# Comm_SQUID.net
KiCad netlist of a schematic drawn in Altium Designer
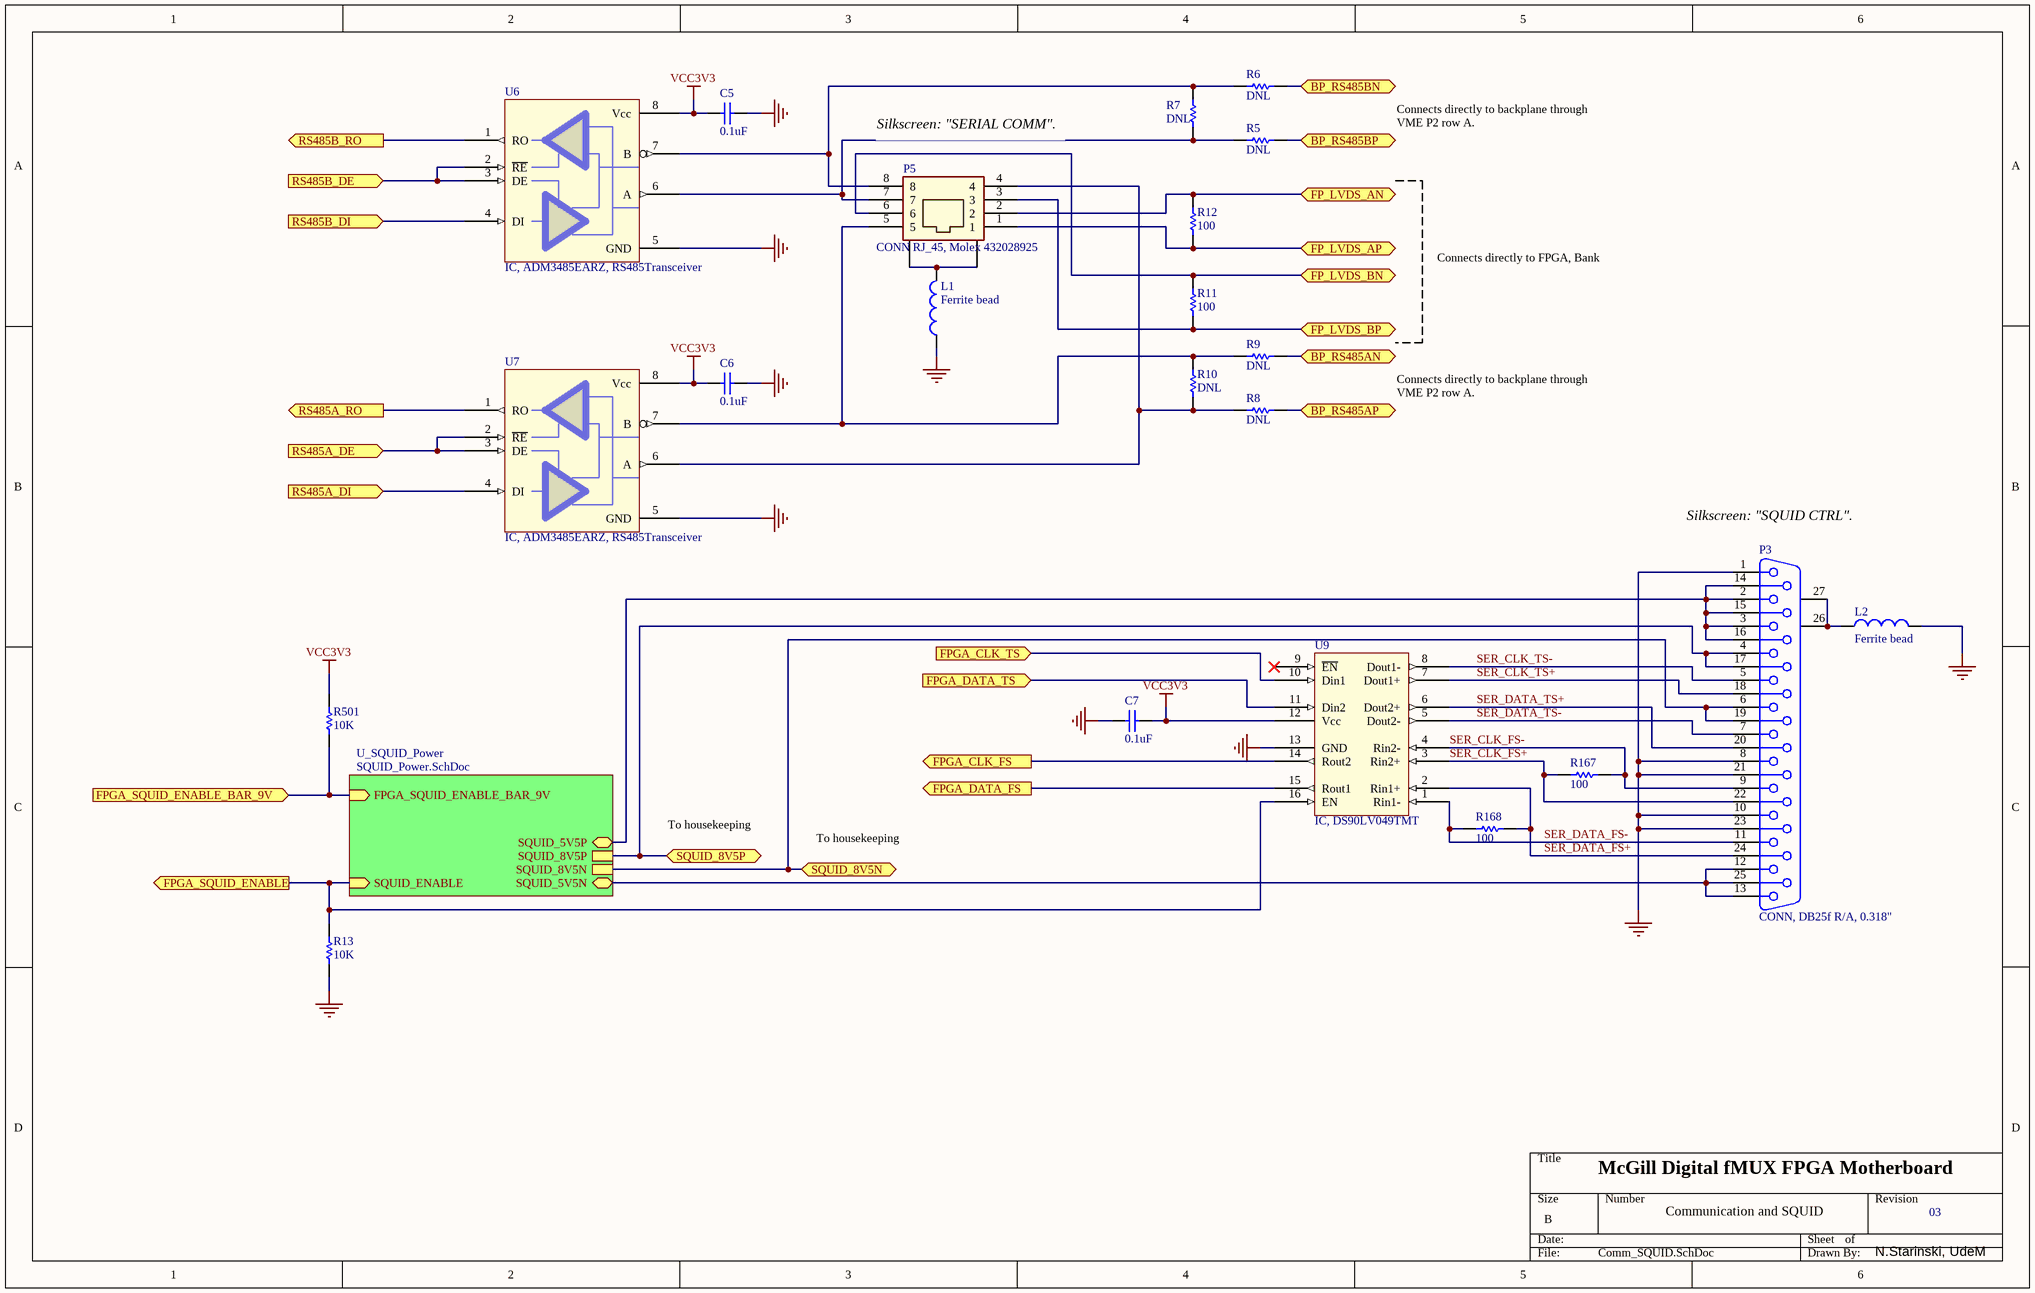
[diagram p0: Comm_SQUID.SchDoc]

(export (version "E")
  (design (tool "Eeschema 10.0.6"))
  (components
    (comp (ref "C5")
      (value "0.1uF")
      (footprint "CC1608-0603")
      (description "Capacitor (Semiconductor SIM Model)")
      (fields (field (name "PUBLISHER") "Altium Limited"))
      (libsource (lib "Miscellaneous Devices") (part "Cap Semi"))
    )
    (comp (ref "C6")
      (value "0.1uF")
      (footprint "CC1608-0603")
      (description "Capacitor (Semiconductor SIM Model)")
      (fields (field (name "PUBLISHER") "Altium Limited"))
      (libsource (lib "Miscellaneous Devices") (part "Cap Semi"))
    )
    (comp (ref "C7")
      (value "0.1uF")
      (footprint "CC1608-0603")
      (description "Capacitor (Semiconductor SIM Model)")
      (fields (field (name "PUBLISHER") "Altium Limited"))
      (libsource (lib "Miscellaneous Devices") (part "Cap Semi"))
    )
    (comp (ref "L1")
      (value "Ferrite bead")
      (footprint "INDC2012-0805")
      (description "Inductor SM 0805")
      (fields (field (name "PUBLISHER") "Altium Limited"))
      (libsource (lib "Miscellaneous Devices") (part "Inductor"))
    )
    (comp (ref "L2")
      (value "Ferrite bead")
      (footprint "INDC2012-0805")
      (description "Inductor SM 0805")
      (fields (field (name "PUBLISHER") "Altium Limited"))
      (libsource (lib "Miscellaneous Devices") (part "Inductor"))
    )
    (comp (ref "P3")
      (value "CONN, DB25f R/A, 0.318\"")
      (footprint "DSUB1.385-2H25A")
      (description "Amp 5747846-4 or ITT DBMG25SJA197")
      (fields (field (name "PUBLISHER") "Altium Limited"))
      (libsource (lib "Miscellaneous Connectors") (part "D Connector 25"))
    )
    (comp (ref "P5")
      (value "CONN RJ_45, Molex 432028925")
      (footprint "RJ45")
      (description "Molex 432028925")
      (libsource (lib "MyComp1") (part "RJ_45"))
    )
    (comp (ref "R5")
      (value "DNL")
      (footprint "CR1608-0603")
      (description "Semiconductor Resistor")
      (fields (field (name "PUBLISHER") "Altium Limited"))
      (libsource (lib "Miscellaneous Devices") (part "Res Semi"))
    )
    (comp (ref "R6")
      (value "DNL")
      (footprint "CR1608-0603")
      (description "Semiconductor Resistor")
      (fields (field (name "PUBLISHER") "Altium Limited"))
      (libsource (lib "Miscellaneous Devices") (part "Res Semi"))
    )
    (comp (ref "R7")
      (value "DNL")
      (footprint "CR1608-0603")
      (description "Semiconductor Resistor")
      (fields (field (name "PUBLISHER") "Altium Limited"))
      (libsource (lib "Miscellaneous Devices 02") (part "Res Semi"))
    )
    (comp (ref "R8")
      (value "DNL")
      (footprint "CR1608-0603")
      (description "Semiconductor Resistor")
      (fields (field (name "PUBLISHER") "Altium Limited"))
      (libsource (lib "Miscellaneous Devices 02") (part "Res Semi"))
    )
    (comp (ref "R9")
      (value "DNL")
      (footprint "CR1608-0603")
      (description "Semiconductor Resistor")
      (fields (field (name "PUBLISHER") "Altium Limited"))
      (libsource (lib "Miscellaneous Devices 02") (part "Res Semi"))
    )
    (comp (ref "R10")
      (value "DNL")
      (footprint "CR1608-0603")
      (description "Semiconductor Resistor")
      (fields (field (name "PUBLISHER") "Altium Limited"))
      (libsource (lib "Miscellaneous Devices 02") (part "Res Semi"))
    )
    (comp (ref "R11")
      (value "100")
      (footprint "CR1608-0603")
      (description "Semiconductor Resistor")
      (fields (field (name "PUBLISHER") "Altium Limited"))
      (libsource (lib "Miscellaneous Devices") (part "Res Semi"))
    )
    (comp (ref "R12")
      (value "100")
      (footprint "CR1608-0603")
      (description "Semiconductor Resistor")
      (fields (field (name "PUBLISHER") "Altium Limited"))
      (libsource (lib "Miscellaneous Devices") (part "Res Semi"))
    )
    (comp (ref "R13")
      (value "10K")
      (footprint "CR1608-0603")
      (description "Resistor 0603")
      (fields (field (name "PUBLISHER") "Altium Limited"))
      (libsource (lib "Miscellaneous Devices") (part "Res Semi"))
    )
    (comp (ref "R167")
      (value "100")
      (footprint "CR1608-0603")
      (description "Semiconductor Resistor")
      (fields (field (name "PUBLISHER") "Altium Limited"))
      (libsource (lib "Miscellaneous Devices") (part "Res Semi"))
    )
    (comp (ref "R168")
      (value "100")
      (footprint "CR1608-0603")
      (description "Semiconductor Resistor")
      (fields (field (name "PUBLISHER") "Altium Limited"))
      (libsource (lib "Miscellaneous Devices") (part "Res Semi"))
    )
    (comp (ref "R501")
      (value "10K")
      (footprint "1608[0603]")
      (description "Semiconductor Resistor")
      (fields (field (name "PUBLISHER") "Altium Limited"))
      (libsource (lib "Miscellaneous Devices") (part "Res Semi"))
    )
    (comp (ref "U6")
      (value "IC, ADM3485EARZ, RS485Transceiver")
      (footprint "SO-G8/Y1.9")
      (description "20 Mbps, EIA RS-485 Transceiver")
      (libsource (lib "RS_transceivers") (part "ADM3485"))
    )
    (comp (ref "U7")
      (value "IC, ADM3485EARZ, RS485Transceiver")
      (footprint "SO-G8/Y1.9")
      (description "20 Mbps, EIA RS-485 Transceiver")
      (libsource (lib "RS_transceivers") (part "ADM3485"))
    )
    (comp (ref "U9")
      (value "IC, DS90LV049TMT")
      (footprint "TSSO5x6-G16")
      (description "3V LVDS Dual Line Transceiver")
      (libsource (lib "NSC Interface Line Transceiver") (part "DS90LV049"))
    )
  )
  (nets
    (net (code "1") (name "/BP_RS485AN") (class "Default")
      (node (ref "R9") (pin "2") (pinfunction "2_2") (pintype "passive"))
    )
    (net (code "2") (name "/BP_RS485AP") (class "Default")
      (node (ref "R8") (pin "2") (pinfunction "2_2") (pintype "passive"))
    )
    (net (code "3") (name "/BP_RS485BN") (class "Default")
      (node (ref "R6") (pin "2") (pinfunction "2_2") (pintype "passive"))
    )
    (net (code "4") (name "/BP_RS485BP") (class "Default")
      (node (ref "R5") (pin "2") (pinfunction "2_2") (pintype "passive"))
    )
    (net (code "5") (name "/FPGA_CLK_FS") (class "Default")
      (node (ref "U9") (pin "14") (pinfunction "Rout2_14") (pintype "output"))
    )
    (net (code "6") (name "/FPGA_CLK_TS") (class "Default")
      (node (ref "U9") (pin "10") (pinfunction "Din1_10") (pintype "input"))
    )
    (net (code "7") (name "/FPGA_DATA_FS") (class "Default")
      (node (ref "U9") (pin "15") (pinfunction "Rout1_15") (pintype "output"))
    )
    (net (code "8") (name "/FPGA_DATA_TS") (class "Default")
      (node (ref "U9") (pin "11") (pinfunction "Din2_11") (pintype "input"))
    )
    (net (code "9") (name "/FPGA_SQUID_ENABLE") (class "Default")
      (node (ref "R13") (pin "2") (pinfunction "2_2") (pintype "passive"))
      (node (ref "U9") (pin "16") (pinfunction "EN_16") (pintype "input"))
    )
    (net (code "10") (name "/FPGA_SQUID_ENABLE_BAR_9V") (class "Default")
      (node (ref "R501") (pin "1") (pinfunction "1_1") (pintype "passive"))
    )
    (net (code "11") (name "/FP_LVDS_AN") (class "Default")
      (node (ref "P5") (pin "2") (pinfunction "2_2") (pintype "passive"))
      (node (ref "R12") (pin "2") (pinfunction "2_2") (pintype "passive"))
    )
    (net (code "12") (name "/FP_LVDS_AP") (class "Default")
      (node (ref "P5") (pin "1") (pinfunction "1_1") (pintype "passive"))
      (node (ref "R12") (pin "1") (pinfunction "1_1") (pintype "passive"))
    )
    (net (code "13") (name "/FP_LVDS_BN") (class "Default")
      (node (ref "P5") (pin "6") (pinfunction "6_6") (pintype "passive"))
      (node (ref "R11") (pin "2") (pinfunction "2_2") (pintype "passive"))
    )
    (net (code "14") (name "/FP_LVDS_BP") (class "Default")
      (node (ref "P5") (pin "3") (pinfunction "3_3") (pintype "passive"))
      (node (ref "R11") (pin "1") (pinfunction "1_1") (pintype "passive"))
    )
    (net (code "15") (name "/RS485A_DE") (class "Default")
      (node (ref "U7") (pin "2") (pinfunction "~{RE}_2") (pintype "input"))
      (node (ref "U7") (pin "3") (pinfunction "DE_3") (pintype "input"))
    )
    (net (code "16") (name "/RS485A_DI") (class "Default")
      (node (ref "U7") (pin "4") (pinfunction "DI_4") (pintype "input"))
    )
    (net (code "17") (name "/RS485A_RO") (class "Default")
      (node (ref "U7") (pin "1") (pinfunction "RO_1") (pintype "output"))
    )
    (net (code "18") (name "/RS485B_DE") (class "Default")
      (node (ref "U6") (pin "2") (pinfunction "~{RE}_2") (pintype "input"))
      (node (ref "U6") (pin "3") (pinfunction "DE_3") (pintype "input"))
    )
    (net (code "19") (name "/RS485B_DI") (class "Default")
      (node (ref "U6") (pin "4") (pinfunction "DI_4") (pintype "input"))
    )
    (net (code "20") (name "/RS485B_RO") (class "Default")
      (node (ref "U6") (pin "1") (pinfunction "RO_1") (pintype "output"))
    )
    (net (code "21") (name "/SER_CLK_FS+") (class "Default")
      (node (ref "P3") (pin "22") (pinfunction "22_22") (pintype "passive"))
      (node (ref "R167") (pin "1") (pinfunction "1_1") (pintype "passive"))
      (node (ref "U9") (pin "3") (pinfunction "Rin2+_3") (pintype "input"))
    )
    (net (code "22") (name "/SER_CLK_FS-") (class "Default")
      (node (ref "P3") (pin "9") (pinfunction "9_9") (pintype "passive"))
      (node (ref "R167") (pin "2") (pinfunction "2_2") (pintype "passive"))
      (node (ref "U9") (pin "4") (pinfunction "Rin2-_4") (pintype "input"))
    )
    (net (code "23") (name "/SER_CLK_TS+") (class "Default")
      (node (ref "P3") (pin "18") (pinfunction "18_18") (pintype "passive"))
      (node (ref "U9") (pin "7") (pinfunction "Dout1+_7") (pintype "output"))
    )
    (net (code "24") (name "/SER_CLK_TS-") (class "Default")
      (node (ref "P3") (pin "5") (pinfunction "5_5") (pintype "passive"))
      (node (ref "U9") (pin "8") (pinfunction "Dout1-_8") (pintype "output"))
    )
    (net (code "25") (name "/SER_DATA_FS+") (class "Default")
      (node (ref "P3") (pin "24") (pinfunction "24_24") (pintype "passive"))
      (node (ref "R168") (pin "2") (pinfunction "2_2") (pintype "passive"))
      (node (ref "U9") (pin "2") (pinfunction "Rin1+_2") (pintype "input"))
    )
    (net (code "26") (name "/SER_DATA_FS-") (class "Default")
      (node (ref "P3") (pin "11") (pinfunction "11_11") (pintype "passive"))
      (node (ref "R168") (pin "1") (pinfunction "1_1") (pintype "passive"))
      (node (ref "U9") (pin "1") (pinfunction "Rin1-_1") (pintype "input"))
    )
    (net (code "27") (name "/SER_DATA_TS+") (class "Default")
      (node (ref "P3") (pin "20") (pinfunction "20_20") (pintype "passive"))
      (node (ref "U9") (pin "6") (pinfunction "Dout2+_6") (pintype "output"))
    )
    (net (code "28") (name "/SER_DATA_TS-") (class "Default")
      (node (ref "P3") (pin "7") (pinfunction "7_7") (pintype "passive"))
      (node (ref "U9") (pin "5") (pinfunction "Dout2-_5") (pintype "output"))
    )
    (net (code "29") (name "/SQUID_5V5N") (class "Default")
      (node (ref "P3") (pin "12") (pinfunction "12_12") (pintype "passive"))
      (node (ref "P3") (pin "13") (pinfunction "13_13") (pintype "passive"))
      (node (ref "P3") (pin "25") (pinfunction "25_25") (pintype "passive"))
    )
    (net (code "30") (name "/SQUID_5V5P") (class "Default")
      (node (ref "P3") (pin "14") (pinfunction "14_14") (pintype "passive"))
      (node (ref "P3") (pin "15") (pinfunction "15_15") (pintype "passive"))
      (node (ref "P3") (pin "16") (pinfunction "16_16") (pintype "passive"))
      (node (ref "P3") (pin "2") (pinfunction "2_2") (pintype "passive"))
      (node (ref "P3") (pin "3") (pinfunction "3_3") (pintype "passive"))
    )
    (net (code "31") (name "/SQUID_8V5N") (class "Default")
      (node (ref "P3") (pin "19") (pinfunction "19_19") (pintype "passive"))
      (node (ref "P3") (pin "6") (pinfunction "6_6") (pintype "passive"))
    )
    (net (code "32") (name "/SQUID_8V5P") (class "Default")
      (node (ref "P3") (pin "17") (pinfunction "17_17") (pintype "passive"))
      (node (ref "P3") (pin "4") (pinfunction "4_4") (pintype "passive"))
    )
    (net (code "33") (name "GND") (class "Default")
      (node (ref "C5") (pin "2") (pinfunction "2_2") (pintype "passive"))
      (node (ref "C6") (pin "2") (pinfunction "2_2") (pintype "passive"))
      (node (ref "C7") (pin "1") (pinfunction "1_1") (pintype "passive"))
      (node (ref "L1") (pin "1") (pinfunction "1_1") (pintype "passive"))
      (node (ref "L2") (pin "2") (pinfunction "2_2") (pintype "passive"))
      (node (ref "P3") (pin "1") (pinfunction "1_1") (pintype "passive"))
      (node (ref "P3") (pin "10") (pinfunction "10_10") (pintype "passive"))
      (node (ref "P3") (pin "21") (pinfunction "21_21") (pintype "passive"))
      (node (ref "P3") (pin "23") (pinfunction "23_23") (pintype "passive"))
      (node (ref "P3") (pin "8") (pinfunction "8_8") (pintype "passive"))
      (node (ref "R13") (pin "1") (pinfunction "1_1") (pintype "passive"))
      (node (ref "U6") (pin "5") (pinfunction "GND_5") (pintype "power_in"))
      (node (ref "U7") (pin "5") (pinfunction "GND_5") (pintype "power_in"))
      (node (ref "U9") (pin "13") (pinfunction "GND_13") (pintype "power_in"))
    )
    (net (code "34") (name "Net-(L1-Pad2)") (class "Default")
      (node (ref "L1") (pin "2") (pinfunction "2_2") (pintype "passive"))
      (node (ref "P5") (pin "10") (pinfunction "GND_10") (pintype "power_in"))
      (node (ref "P5") (pin "9") (pinfunction "GND_9") (pintype "power_in"))
    )
    (net (code "35") (name "Net-(P3-MH1)") (class "Default")
      (node (ref "L2") (pin "1") (pinfunction "1_1") (pintype "passive"))
      (node (ref "P3") (pin "26") (pinfunction "MH1_26") (pintype "passive"))
      (node (ref "P3") (pin "27") (pinfunction "MH2_27") (pintype "passive"))
    )
    (net (code "36") (name "Net-(U6-A)") (class "Default")
      (node (ref "P5") (pin "7") (pinfunction "7_7") (pintype "passive"))
      (node (ref "R5") (pin "1") (pinfunction "1_1") (pintype "passive"))
      (node (ref "R7") (pin "1") (pinfunction "1_1") (pintype "passive"))
      (node (ref "U6") (pin "6") (pinfunction "A_6") (pintype "output"))
    )
    (net (code "37") (name "Net-(U6-B)") (class "Default")
      (node (ref "P5") (pin "8") (pinfunction "8_8") (pintype "passive"))
      (node (ref "R6") (pin "1") (pinfunction "1_1") (pintype "passive"))
      (node (ref "R7") (pin "2") (pinfunction "2_2") (pintype "passive"))
      (node (ref "U6") (pin "7") (pinfunction "B_7") (pintype "output"))
    )
    (net (code "38") (name "Net-(U7-A)") (class "Default")
      (node (ref "P5") (pin "4") (pinfunction "4_4") (pintype "passive"))
      (node (ref "R10") (pin "1") (pinfunction "1_1") (pintype "passive"))
      (node (ref "R8") (pin "1") (pinfunction "1_1") (pintype "passive"))
      (node (ref "U7") (pin "6") (pinfunction "A_6") (pintype "output"))
    )
    (net (code "39") (name "Net-(U7-B)") (class "Default")
      (node (ref "P5") (pin "5") (pinfunction "5_5") (pintype "passive"))
      (node (ref "R10") (pin "2") (pinfunction "2_2") (pintype "passive"))
      (node (ref "R9") (pin "1") (pinfunction "1_1") (pintype "passive"))
      (node (ref "U7") (pin "7") (pinfunction "B_7") (pintype "output"))
    )
    (net (code "40") (name "VCC3V3") (class "Default")
      (node (ref "C5") (pin "1") (pinfunction "1_1") (pintype "passive"))
      (node (ref "C6") (pin "1") (pinfunction "1_1") (pintype "passive"))
      (node (ref "C7") (pin "2") (pinfunction "2_2") (pintype "passive"))
      (node (ref "R501") (pin "2") (pinfunction "2_2") (pintype "passive"))
      (node (ref "U6") (pin "8") (pinfunction "Vcc_8") (pintype "power_in"))
      (node (ref "U7") (pin "8") (pinfunction "Vcc_8") (pintype "power_in"))
      (node (ref "U9") (pin "12") (pinfunction "Vcc_12") (pintype "power_in"))
    )
    (net (code "41") (name "unconnected-(U9-~{EN}-Pad9)") (class "Default")
      (node (ref "U9") (pin "9") (pinfunction "~{EN}_9") (pintype "input+no_connect"))
    )
  )
)
